# FMC_DAC_1_5GS_4CH.net
KiCad netlist of a schematic drawn in Altium Designer
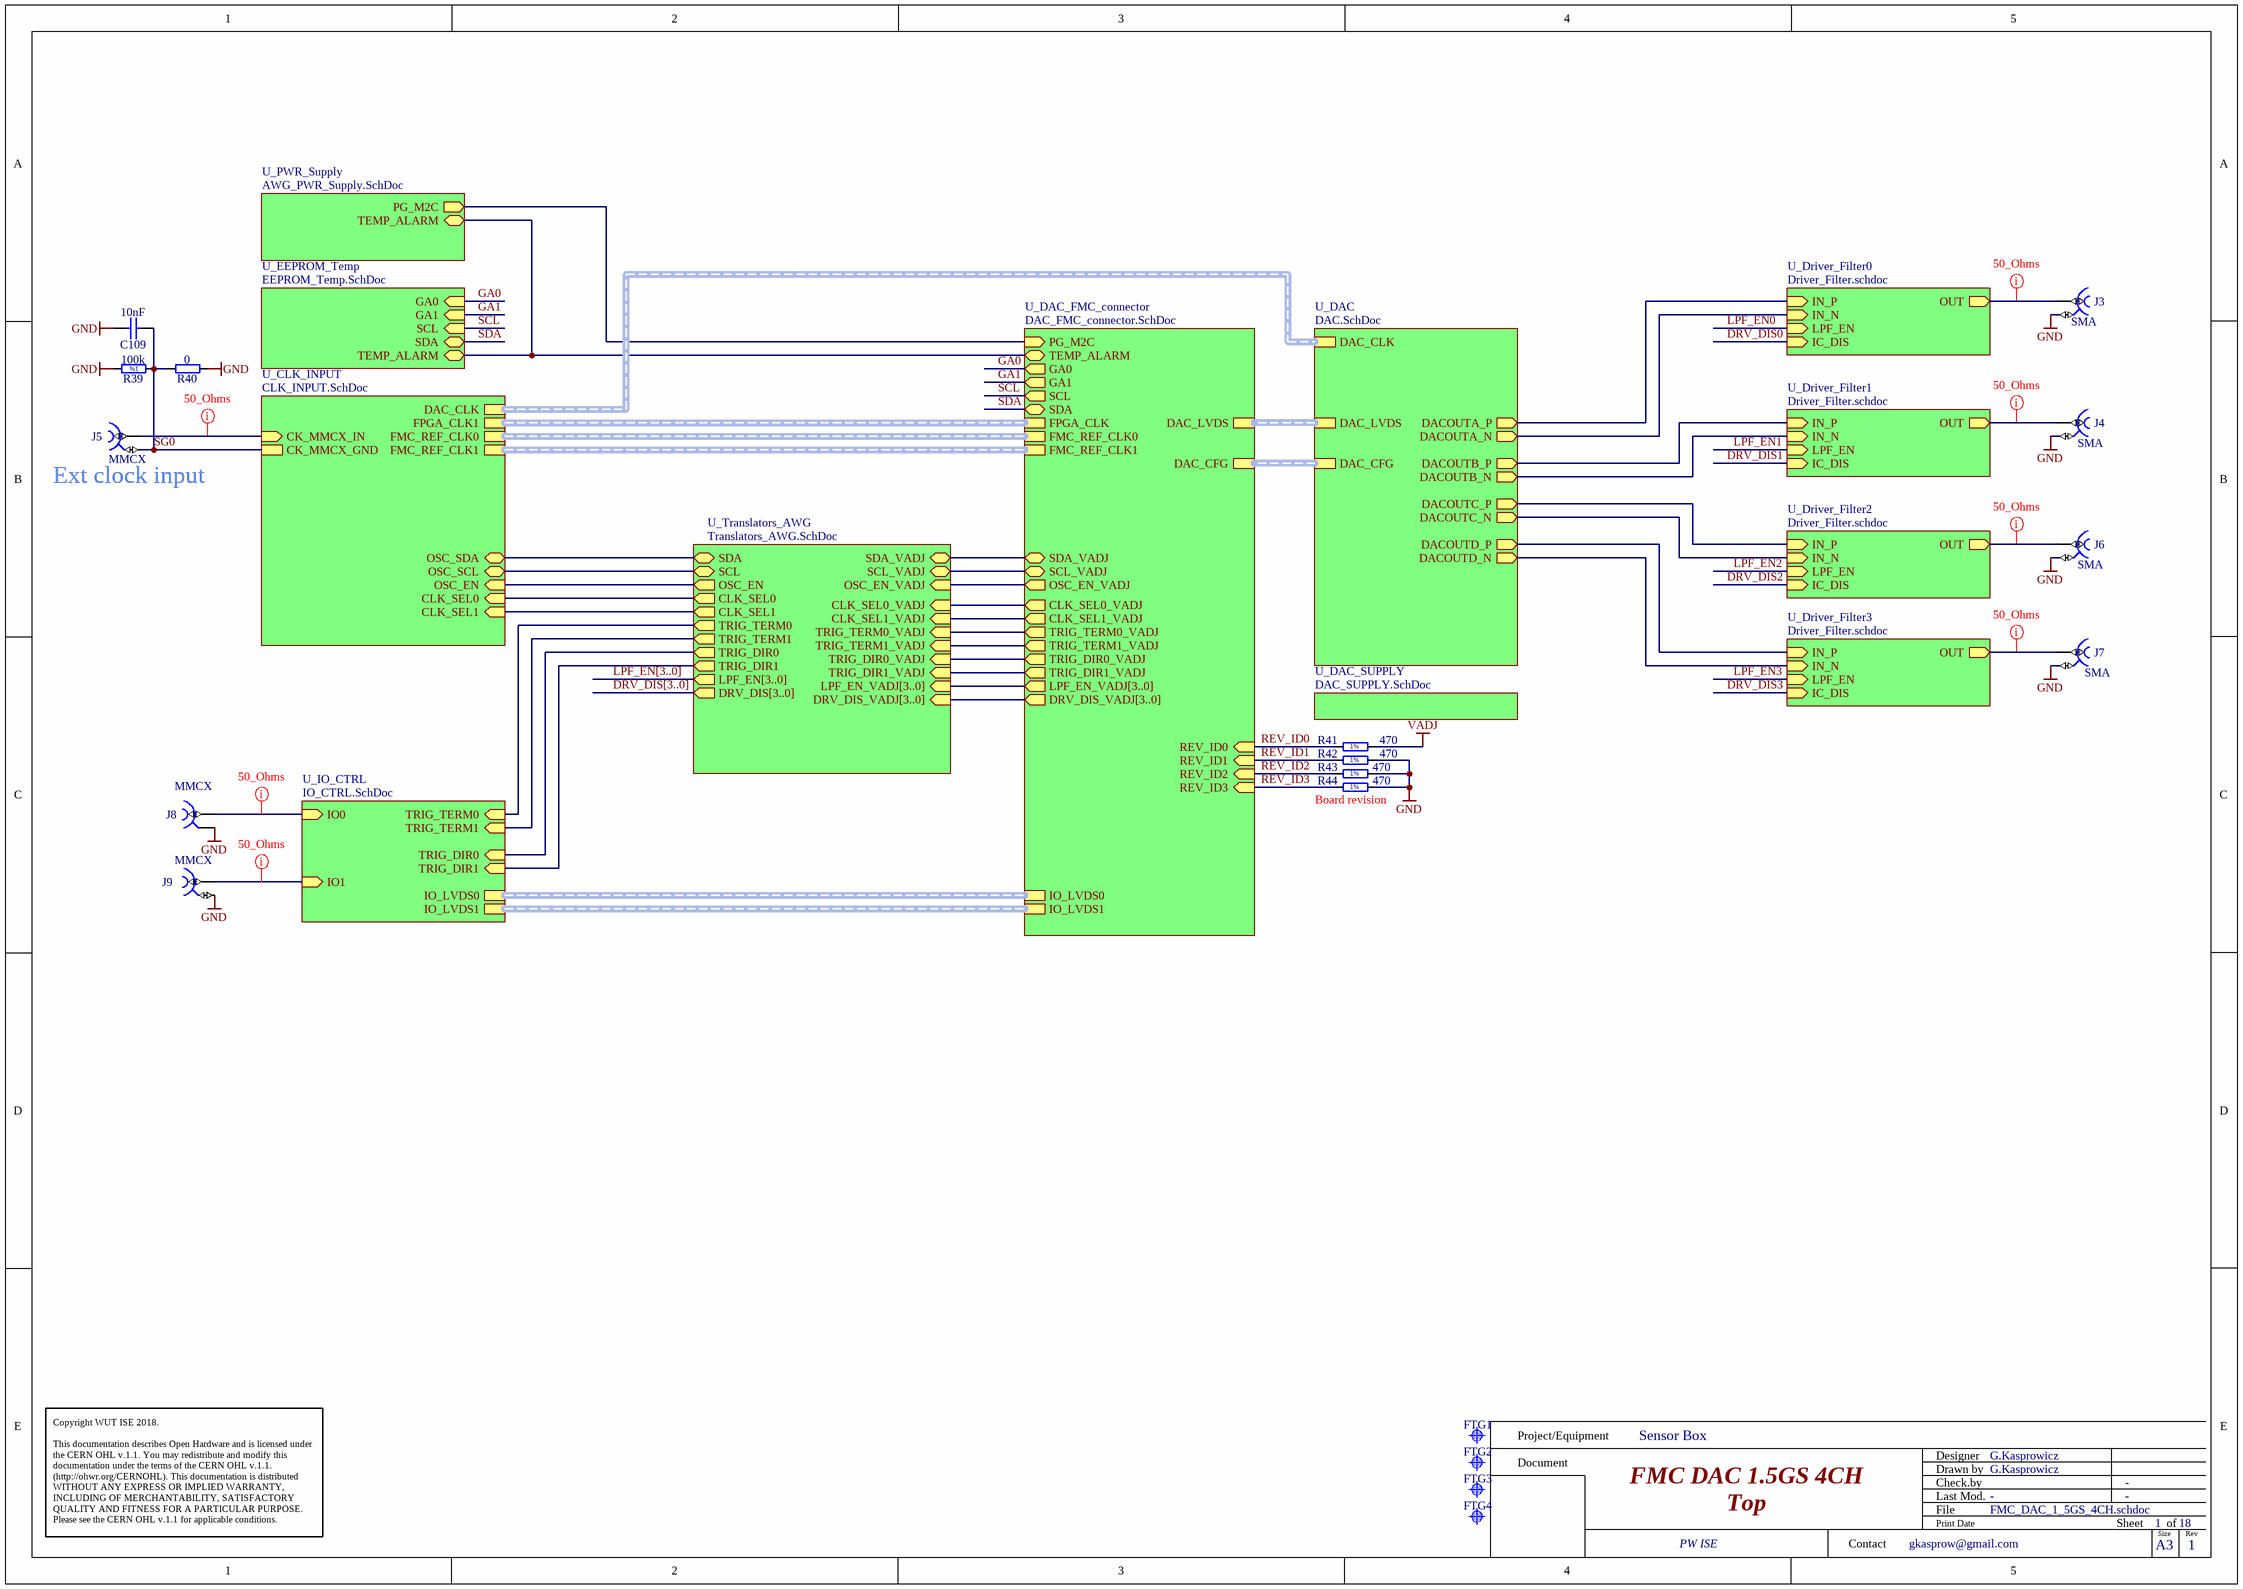
[diagram p0: FMC_DAC_1_5GS_4CH.schdoc]

(export (version "E")
  (design (tool "Eeschema 10.0.6"))
  (components
    (comp (ref "C109")
      (value "10nF")
      (footprint "CAPC1005X55N")
      (description "Non-polarised capacitor")
      (fields
        (field (name "PART NUMBER") "CC0402_10NF_16V_10%_X7R")
        (field (name "VOLTAGE") "16V")
        (field (name "AUTHOR") "CERN DEM JLC")
      )
      (libsource (lib "Capacitors") (part "Capacitor - non polarized"))
    )
    (comp (ref "FTG1")
      (value "Use only in PCB")
      (footprint "FIDUCIAL_TOP_C100-200")
      (description "Fiducial Target")
      (fields (field (name "PART NUMBER") "FIDUCIAL_TARGET_C100-200") (field (name "AUTHOR") "CERN DEM JLC"))
      (libsource (lib "Eletro-mechanical") (part "Fiducial Target"))
    )
    (comp (ref "FTG2")
      (value "Use only in PCB")
      (footprint "FIDUCIAL_TOP_S100-200")
      (description "Fiducial Target")
      (fields (field (name "PART NUMBER") "FIDUCIAL_TARGET_S100-200") (field (name "AUTHOR") "CERN DEM JLC"))
      (libsource (lib "Eletro-mechanical") (part "Fiducial Target"))
    )
    (comp (ref "FTG3")
      (value "Use only in PCB")
      (footprint "FIDUCIAL_TOP_S100-200")
      (description "Fiducial Target")
      (fields (field (name "PART NUMBER") "FIDUCIAL_TARGET_S100-200") (field (name "AUTHOR") "CERN DEM JLC"))
      (libsource (lib "Eletro-mechanical") (part "Fiducial Target"))
    )
    (comp (ref "FTG4")
      (value "Use only in PCB")
      (footprint "FIDUCIAL_TOP_S100-200")
      (description "Fiducial Target")
      (fields (field (name "PART NUMBER") "FIDUCIAL_TARGET_S100-200") (field (name "AUTHOR") "CERN DEM JLC"))
      (libsource (lib "Eletro-mechanical") (part "Fiducial Target"))
    )
    (comp (ref "J3")
      (value "SMA")
      (footprint "AMPHENOL_901-143")
      (fields
        (field (name "PART NUMBER") "AMPHENOL_901-143")
        (field (name "MANUFACTURER") "AMPHENOL")
        (field (name "MANUFACTURER PART NUMBER") "901-143")
        (field (name "AUTHOR") "LNLS DIG GBMB")
      )
      (libsource (lib "FMC_ADC_250M_16B_4ch") (part "Coax_1Female_1Shield"))
    )
    (comp (ref "J4")
      (value "SMA")
      (footprint "AMPHENOL_901-143")
      (fields
        (field (name "PART NUMBER") "AMPHENOL_901-143")
        (field (name "MANUFACTURER") "AMPHENOL")
        (field (name "MANUFACTURER PART NUMBER") "901-143")
        (field (name "AUTHOR") "LNLS DIG GBMB")
      )
      (libsource (lib "FMC_ADC_250M_16B_4ch") (part "Coax_1Female_1Shield"))
    )
    (comp (ref "J5")
      (value "Coax_1Female_1Shield")
      (footprint "HUBER-SUHNER_85_MMCX-50-0-1/111 OH")
      (fields
        (field (name "PART NUMBER") "HUBER-SUHNER_85_MMCX-50-0-1/111 OH")
        (field (name "FAMILY") "MMCX")
        (field (name "MANUFACTURER") "HUBER+SUHNER")
        (field (name "MANUFACTURER PART NUMBER") "85_MMCX-50-0-1/111 OH")
        (field (name "AUTHOR") "CERN DEM JLC")
      )
      (libsource (lib "Connectors") (part "Coax_1Female_1Shield"))
    )
    (comp (ref "J6")
      (value "SMA")
      (footprint "AMPHENOL_901-143")
      (fields
        (field (name "PART NUMBER") "AMPHENOL_901-143")
        (field (name "MANUFACTURER") "AMPHENOL")
        (field (name "MANUFACTURER PART NUMBER") "901-143")
        (field (name "AUTHOR") "LNLS DIG GBMB")
      )
      (libsource (lib "FMC_ADC_250M_16B_4ch") (part "Coax_1Female_1Shield"))
    )
    (comp (ref "J7")
      (value "SMA")
      (footprint "AMPHENOL_901-143")
      (fields
        (field (name "PART NUMBER") "AMPHENOL_901-143")
        (field (name "MANUFACTURER") "AMPHENOL")
        (field (name "MANUFACTURER PART NUMBER") "901-143")
        (field (name "AUTHOR") "LNLS DIG GBMB")
      )
      (libsource (lib "FMC_ADC_250M_16B_4ch") (part "Coax_1Female_1Shield"))
    )
    (comp (ref "J8")
      (value "Coax_1Female_1Shield")
      (footprint "HUBER-SUHNER_85_MMCX-50-0-1/111 OH")
      (fields
        (field (name "PART NUMBER") "HUBER-SUHNER_85_MMCX-50-0-1/111 OH")
        (field (name "FAMILY") "MMCX")
        (field (name "MANUFACTURER") "HUBER+SUHNER")
        (field (name "MANUFACTURER PART NUMBER") "85_MMCX-50-0-1/111 OH")
        (field (name "AUTHOR") "CERN DEM JLC")
      )
      (libsource (lib "Connectors") (part "Coax_1Female_1Shield"))
    )
    (comp (ref "J9")
      (value "Coax_1Female_1Shield")
      (footprint "HUBER-SUHNER_85_MMCX-50-0-1/111 OH")
      (fields
        (field (name "PART NUMBER") "HUBER-SUHNER_85_MMCX-50-0-1/111 OH")
        (field (name "FAMILY") "MMCX")
        (field (name "MANUFACTURER") "HUBER+SUHNER")
        (field (name "MANUFACTURER PART NUMBER") "85_MMCX-50-0-1/111 OH")
        (field (name "AUTHOR") "CERN DEM JLC")
      )
      (libsource (lib "Connectors") (part "Coax_1Female_1Shield"))
    )
    (comp (ref "R39")
      (value "100k")
      (footprint "RESC1005X40N")
      (description "Resistor - 1%")
      (fields
        (field (name "PART NUMBER") "R0402_100K_1%_0.0625W_100PPM")
        (field (name "MANUFACTURER") "GENERIC")
        (field (name "AUTHOR") "CERN DEM JLC")
      )
      (libsource (lib "Resistors") (part "Resistor - 1%"))
    )
    (comp (ref "R40")
      (value "0")
      (footprint "RESC1608X55N")
      (description "Resistor")
      (fields
        (field (name "PART NUMBER") "R0603_0R_JUMPER")
        (field (name "MANUFACTURER") "GENERIC")
        (field (name "AUTHOR") "CERN DEM JLC")
      )
      (libsource (lib "Resistors") (part "Resistor"))
    )
    (comp (ref "R41")
      (value "470")
      (footprint "RESC1005X40N")
      (description "Resistor - 1%")
      (fields
        (field (name "PART NUMBER") "R0402_470R_1%_0.0625W_100PPM")
        (field (name "POWER") "0.0625W")
        (field (name "AUTHOR") "CERN DEM JLC")
      )
      (libsource (lib "Resistors") (part "Resistor - 1%"))
    )
    (comp (ref "R42")
      (value "470")
      (footprint "RESC1005X40N")
      (description "Resistor - 1%")
      (fields
        (field (name "PART NUMBER") "R0402_470R_1%_0.0625W_100PPM")
        (field (name "POWER") "0.0625W")
        (field (name "AUTHOR") "CERN DEM JLC")
      )
      (libsource (lib "Resistors") (part "Resistor - 1%"))
    )
    (comp (ref "R43")
      (value "470")
      (footprint "RESC1005X40N")
      (description "Resistor - 1%")
      (fields
        (field (name "PART NUMBER") "R0402_470R_1%_0.0625W_100PPM")
        (field (name "POWER") "0.0625W")
        (field (name "AUTHOR") "CERN DEM JLC")
      )
      (libsource (lib "Resistors") (part "Resistor - 1%"))
    )
    (comp (ref "R44")
      (value "470")
      (footprint "RESC1005X40N")
      (description "Resistor - 1%")
      (fields
        (field (name "PART NUMBER") "R0402_470R_1%_0.0625W_100PPM")
        (field (name "POWER") "0.0625W")
        (field (name "AUTHOR") "CERN DEM JLC")
      )
      (libsource (lib "Resistors") (part "Resistor - 1%"))
    )
  )
  (nets
    (net (code "1") (name "/CK_MMCX_IN") (class "Default")
      (node (ref "J5") (pin "1") (pinfunction "1_1") (pintype "bidirectional"))
    )
    (net (code "28") (name "/IO0") (class "Default")
      (node (ref "J8") (pin "1") (pinfunction "1_1") (pintype "bidirectional"))
    )
    (net (code "29") (name "/IO1") (class "Default")
      (node (ref "J9") (pin "1") (pinfunction "1_1") (pintype "bidirectional"))
    )
    (net (code "42") (name "/OUT") (class "Default")
      (node (ref "J3") (pin "1") (pinfunction "1_1") (pintype "bidirectional"))
    )
    (net (code "43") (name "/OUT_1") (class "Default")
      (node (ref "J6") (pin "1") (pinfunction "1_1") (pintype "bidirectional"))
    )
    (net (code "44") (name "/OUT_2") (class "Default")
      (node (ref "J7") (pin "1") (pinfunction "1_1") (pintype "bidirectional"))
    )
    (net (code "45") (name "/OUT_3") (class "Default")
      (node (ref "J4") (pin "1") (pinfunction "1_1") (pintype "bidirectional"))
    )
    (net (code "47") (name "/REV_ID0") (class "Default")
      (node (ref "R41") (pin "1") (pinfunction "1_1") (pintype "passive"))
    )
    (net (code "48") (name "/REV_ID1") (class "Default")
      (node (ref "R42") (pin "1") (pinfunction "1_1") (pintype "passive"))
    )
    (net (code "49") (name "/REV_ID2") (class "Default")
      (node (ref "R43") (pin "1") (pinfunction "1_1") (pintype "passive"))
    )
    (net (code "50") (name "/REV_ID3") (class "Default")
      (node (ref "R44") (pin "1") (pinfunction "1_1") (pintype "passive"))
    )
    (net (code "55") (name "/SG0") (class "Default")
      (node (ref "C109") (pin "1") (pinfunction "1_1") (pintype "passive"))
      (node (ref "J5") (pin "2") (pinfunction "2_2") (pintype "bidirectional"))
      (node (ref "R39") (pin "2") (pinfunction "2_2") (pintype "passive"))
      (node (ref "R40") (pin "2") (pinfunction "2_2") (pintype "passive"))
    )
    (net (code "65") (name "GND") (class "Default")
      (node (ref "C109") (pin "2") (pinfunction "2_2") (pintype "passive"))
      (node (ref "J3") (pin "2") (pinfunction "2_2") (pintype "bidirectional"))
      (node (ref "J4") (pin "2") (pinfunction "2_2") (pintype "bidirectional"))
      (node (ref "J6") (pin "2") (pinfunction "2_2") (pintype "bidirectional"))
      (node (ref "J7") (pin "2") (pinfunction "2_2") (pintype "bidirectional"))
      (node (ref "J8") (pin "2") (pinfunction "2_2") (pintype "bidirectional"))
      (node (ref "J9") (pin "2") (pinfunction "2_2") (pintype "bidirectional"))
      (node (ref "R39") (pin "1") (pinfunction "1_1") (pintype "passive"))
      (node (ref "R40") (pin "1") (pinfunction "1_1") (pintype "passive"))
      (node (ref "R42") (pin "2") (pinfunction "2_2") (pintype "passive"))
      (node (ref "R43") (pin "2") (pinfunction "2_2") (pintype "passive"))
      (node (ref "R44") (pin "2") (pinfunction "2_2") (pintype "passive"))
    )
    (net (code "66") (name "VADJ") (class "Default")
      (node (ref "R41") (pin "2") (pinfunction "2_2") (pintype "passive"))
    )
  )
)
